# TT1-1-Top.net
KiCad netlist of a schematic drawn in Altium Designer
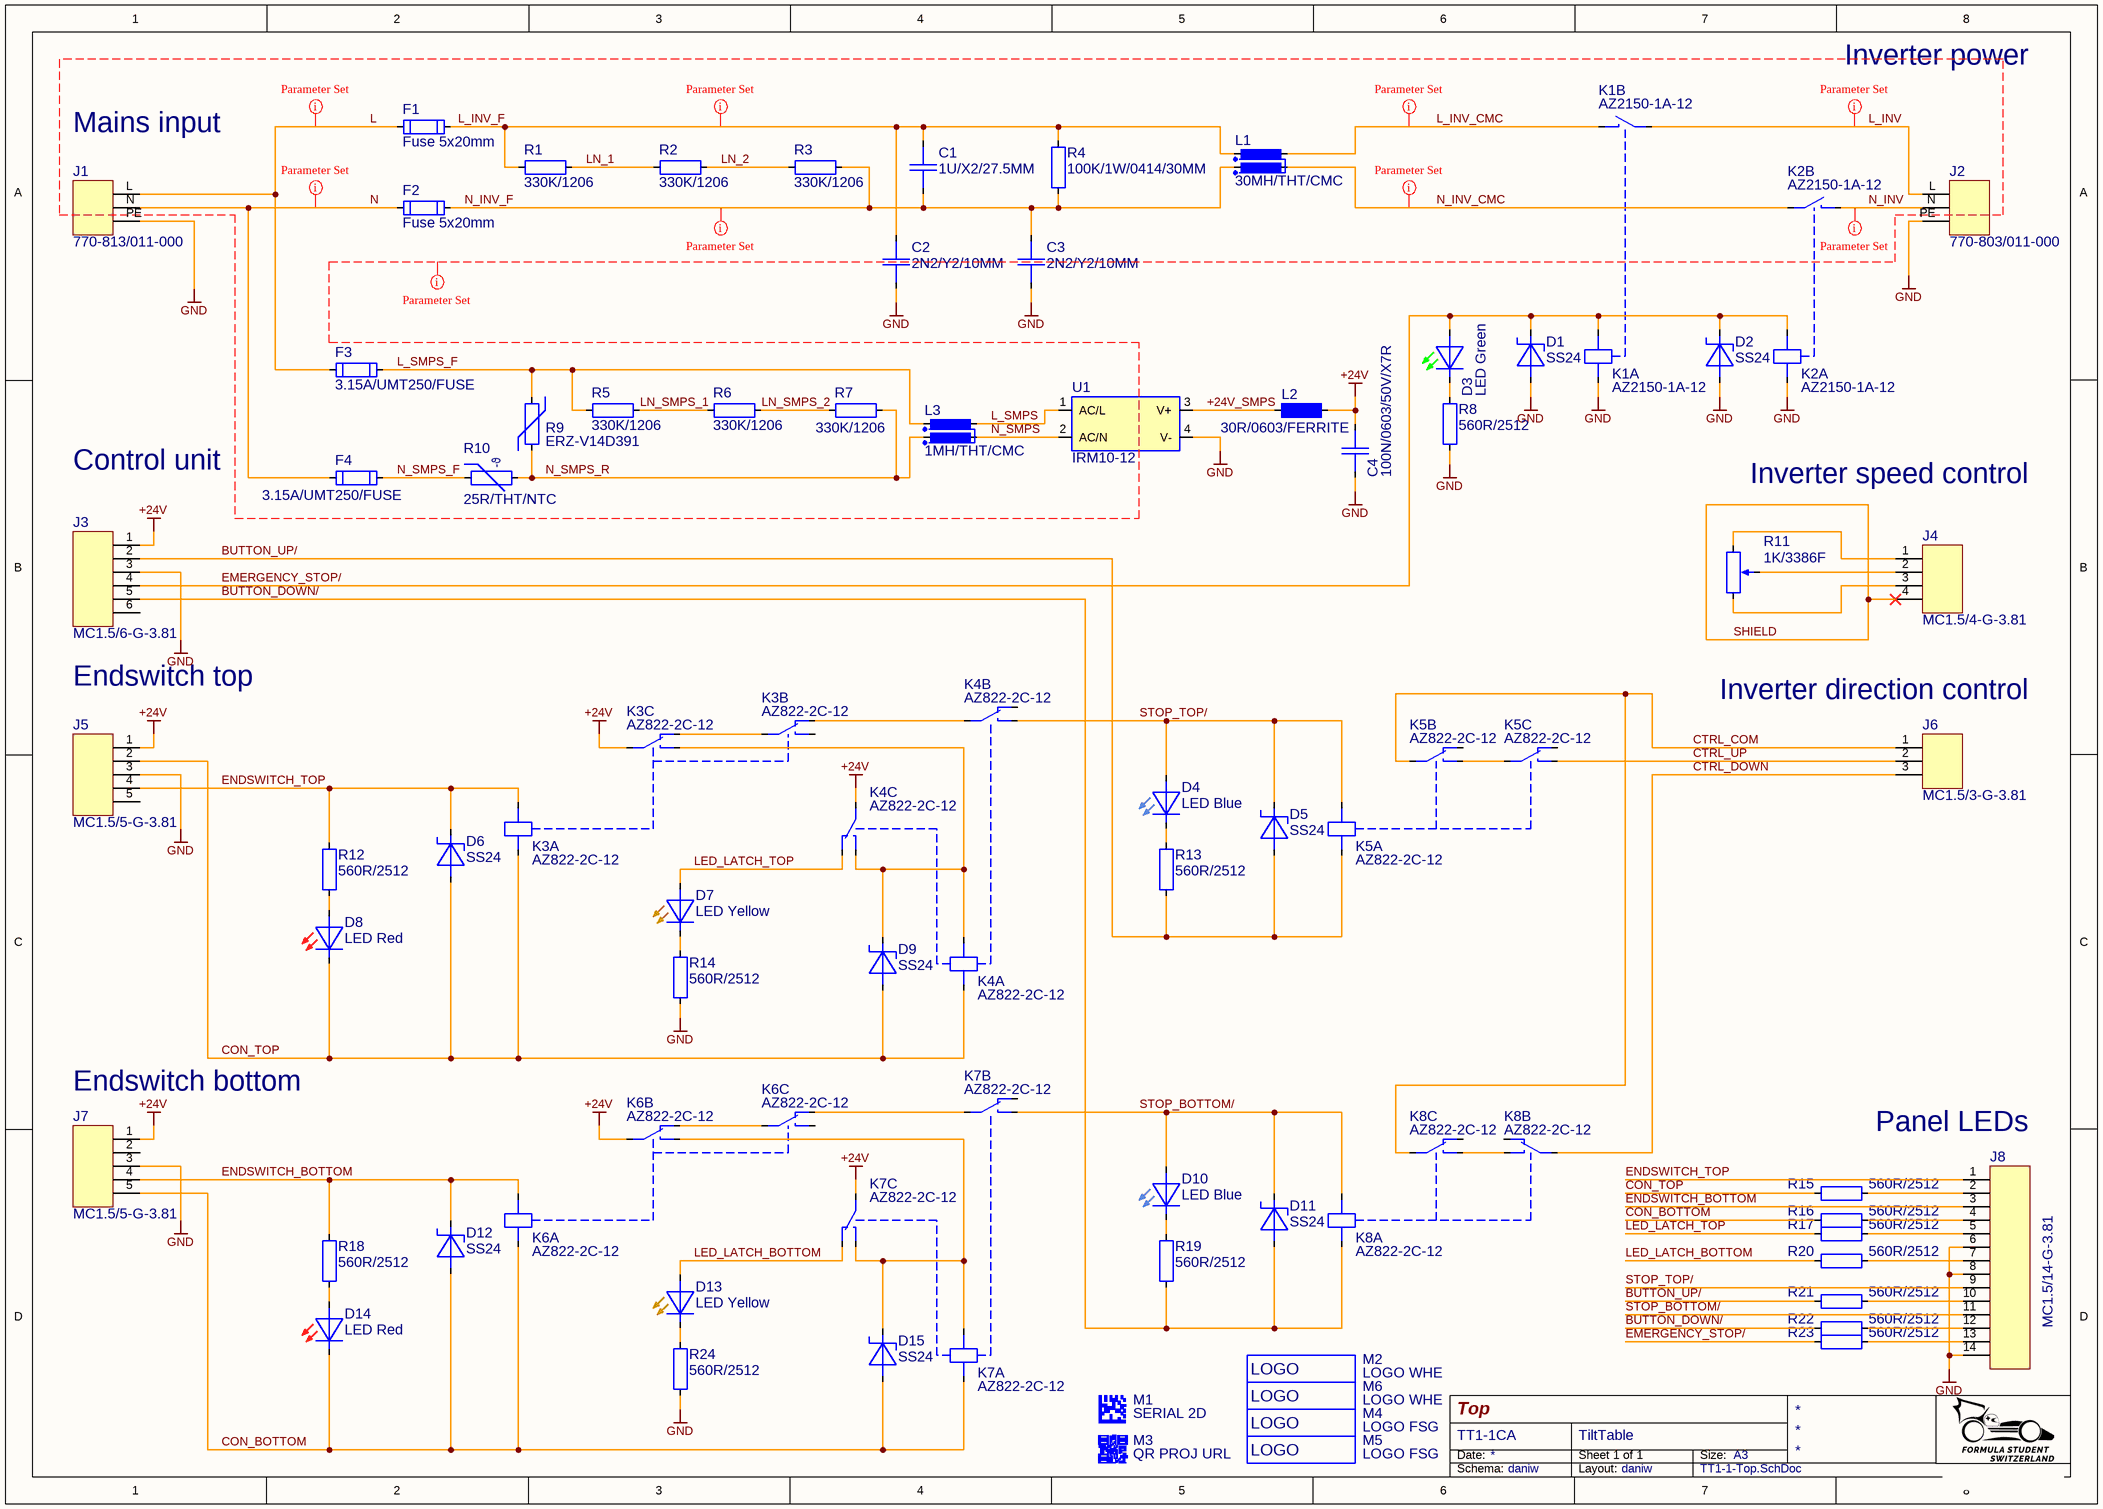
[diagram p0: TT1-1-Top.SchDoc]

(export (version "E")
  (design (tool "Eeschema 10.0.6"))
  (components
    (comp (ref "C1")
      (value "1U/X2/27.5MM")
      (footprint "CAP2750P315X110X190-BL")
      (description "CAP THT 31.5X11X19 1uF 305V X2")
      (fields (field (name "MANUFACTURER") "GENERIC"))
      (libsource (lib "daniw_altium_lib") (part "C"))
    )
    (comp (ref "C2")
      (value "2N2/Y2/10MM")
      (footprint "CAP1000P130X40X90-BL")
      (description "CAP THT 13X4X9 2.2nF 300V Y2")
      (fields (field (name "MANUFACTURER") "GENERIC"))
      (libsource (lib "daniw_altium_lib") (part "C"))
    )
    (comp (ref "C3")
      (value "2N2/Y2/10MM")
      (footprint "CAP1000P130X40X90-BL")
      (description "CAP THT 13X4X9 2.2nF 300V Y2")
      (fields (field (name "MANUFACTURER") "GENERIC"))
      (libsource (lib "daniw_altium_lib") (part "C"))
    )
    (comp (ref "C4")
      (value "100N/0603/50V/X7R")
      (footprint "CAP0603_X7R")
      (description "CAP SM 0603 100nF 50V X7R")
      (fields (field (name "MANUFACTURER") "GENERIC"))
      (libsource (lib "daniw_altium_lib") (part "C"))
    )
    (comp (ref "D1")
      (value "SS24")
      (footprint "DIOM5226X230")
      (description "Si Shottky Diode 2A DO-214AC")
      (fields (field (name "MANUFACTURER") "MSKSEMI"))
      (libsource (lib "daniw_altium_lib") (part "D_Schottky"))
    )
    (comp (ref "D2")
      (value "SS24")
      (footprint "DIOM5226X230")
      (description "Si Shottky Diode 2A DO-214AC")
      (fields (field (name "MANUFACTURER") "MSKSEMI"))
      (libsource (lib "daniw_altium_lib") (part "D_Schottky"))
    )
    (comp (ref "D3")
      (value "LED Green")
      (footprint "LED0603_GREEN")
      (description "Generic LED Green 0603")
      (fields (field (name "PART NUMBER") "LED Green 0603") (field (name "MANUFACTURER") "GENERIC"))
      (libsource (lib "daniw_altium_lib") (part "LED_GREEN"))
    )
    (comp (ref "D4")
      (value "LED Blue")
      (footprint "LED0603_BLUE")
      (description "Generic LED Blue 0603")
      (fields (field (name "PART NUMBER") "LED Blue 0603") (field (name "MANUFACTURER") "GENERIC"))
      (libsource (lib "daniw_altium_lib") (part "LED_BLUE"))
    )
    (comp (ref "D5")
      (value "SS24")
      (footprint "DIOM5226X230")
      (description "Si Shottky Diode 2A DO-214AC")
      (fields (field (name "MANUFACTURER") "MSKSEMI"))
      (libsource (lib "daniw_altium_lib") (part "D_Schottky"))
    )
    (comp (ref "D6")
      (value "SS24")
      (footprint "DIOM5226X230")
      (description "Si Shottky Diode 2A DO-214AC")
      (fields (field (name "MANUFACTURER") "MSKSEMI"))
      (libsource (lib "daniw_altium_lib") (part "D_Schottky"))
    )
    (comp (ref "D7")
      (value "LED Yellow")
      (footprint "LED0603_YELLOW")
      (description "Generic LED Yellow 0603")
      (fields (field (name "PART NUMBER") "LED Yellow 0603") (field (name "MANUFACTURER") "GENERIC"))
      (libsource (lib "daniw_altium_lib") (part "LED_YELLOW"))
    )
    (comp (ref "D8")
      (value "LED Red")
      (footprint "LED0603_RED")
      (description "Generic LED Red 0603")
      (fields (field (name "PART NUMBER") "LED Red 0603") (field (name "MANUFACTURER") "GENERIC"))
      (libsource (lib "daniw_altium_lib") (part "LED_RED"))
    )
    (comp (ref "D9")
      (value "SS24")
      (footprint "DIOM5226X230")
      (description "Si Shottky Diode 2A DO-214AC")
      (fields (field (name "MANUFACTURER") "MSKSEMI"))
      (libsource (lib "daniw_altium_lib") (part "D_Schottky"))
    )
    (comp (ref "D10")
      (value "LED Blue")
      (footprint "LED0603_BLUE")
      (description "Generic LED Blue 0603")
      (fields (field (name "PART NUMBER") "LED Blue 0603") (field (name "MANUFACTURER") "GENERIC"))
      (libsource (lib "daniw_altium_lib") (part "LED_BLUE"))
    )
    (comp (ref "D11")
      (value "SS24")
      (footprint "DIOM5226X230")
      (description "Si Shottky Diode 2A DO-214AC")
      (fields (field (name "MANUFACTURER") "MSKSEMI"))
      (libsource (lib "daniw_altium_lib") (part "D_Schottky"))
    )
    (comp (ref "D12")
      (value "SS24")
      (footprint "DIOM5226X230")
      (description "Si Shottky Diode 2A DO-214AC")
      (fields (field (name "MANUFACTURER") "MSKSEMI"))
      (libsource (lib "daniw_altium_lib") (part "D_Schottky"))
    )
    (comp (ref "D13")
      (value "LED Yellow")
      (footprint "LED0603_YELLOW")
      (description "Generic LED Yellow 0603")
      (fields (field (name "PART NUMBER") "LED Yellow 0603") (field (name "MANUFACTURER") "GENERIC"))
      (libsource (lib "daniw_altium_lib") (part "LED_YELLOW"))
    )
    (comp (ref "D14")
      (value "LED Red")
      (footprint "LED0603_RED")
      (description "Generic LED Red 0603")
      (fields (field (name "PART NUMBER") "LED Red 0603") (field (name "MANUFACTURER") "GENERIC"))
      (libsource (lib "daniw_altium_lib") (part "LED_RED"))
    )
    (comp (ref "D15")
      (value "SS24")
      (footprint "DIOM5226X230")
      (description "Si Shottky Diode 2A DO-214AC")
      (fields (field (name "MANUFACTURER") "MSKSEMI"))
      (libsource (lib "daniw_altium_lib") (part "D_Schottky"))
    )
    (comp (ref "F1")
      (value "Fuse 5x20mm")
      (footprint "OGN_THR")
      (description "open fuse holder, 5 x 20 mm, THR, IEC 60335-1")
      (fields (field (name "PART NUMBER") "Fuse/5x20mm/OGN") (field (name "MANUFACTURER") "Schurter"))
      (libsource (lib "daniw_altium_lib") (part "Fuse"))
    )
    (comp (ref "F2")
      (value "Fuse 5x20mm")
      (footprint "OGN_THR")
      (description "open fuse holder, 5 x 20 mm, THR, IEC 60335-1")
      (fields (field (name "PART NUMBER") "Fuse/5x20mm/OGN") (field (name "MANUFACTURER") "Schurter"))
      (libsource (lib "daniw_altium_lib") (part "Fuse"))
    )
    (comp (ref "F3")
      (value "3.15A/UMT250/FUSE")
      (footprint "UMT250")
      (description "Fuse 250VAC 3.15A UMT250")
      (fields (field (name "MANUFACTURER") "Schurter"))
      (libsource (lib "daniw_altium_lib") (part "Fuse"))
    )
    (comp (ref "F4")
      (value "3.15A/UMT250/FUSE")
      (footprint "UMT250")
      (description "Fuse 250VAC 3.15A UMT250")
      (fields (field (name "MANUFACTURER") "Schurter"))
      (libsource (lib "daniw_altium_lib") (part "Fuse"))
    )
    (comp (ref "J1")
      (value "770-813/011-000")
      (footprint "770-813/011-000")
      (description "Wago 770-813/011-000")
      (fields (field (name "MANUFACTURER") "Wago"))
      (libsource (lib "daniw_altium_lib") (part "CON3_MAINS"))
    )
    (comp (ref "J2")
      (value "770-803/011-000")
      (footprint "770-803/011-000")
      (description "Wago 770-803/011-000")
      (fields (field (name "MANUFACTURER") "Wago"))
      (libsource (lib "") (part "CON3_MAINS_1"))
    )
    (comp (ref "J3")
      (value "MC1.5/6-G-3.81")
      (footprint "MC1.5/6-G-3.81")
      (description "Phoenix contact MC 1,5/ 6-G-3,81")
      (fields (field (name "MANUFACTURER") "Phoenix"))
      (libsource (lib "daniw_altium_lib") (part "CON6"))
    )
    (comp (ref "J4")
      (value "MC1.5/4-G-3.81")
      (footprint "MC1.5/4-G-3.81")
      (description "Phoenix contact MC 1,5/ 4-G-3,81")
      (fields (field (name "MANUFACTURER") "Phoenix"))
      (libsource (lib "daniw_altium_lib") (part "CON4"))
    )
    (comp (ref "J5")
      (value "MC1.5/5-G-3.81")
      (footprint "MC1.5/5-G-3.81")
      (description "Phoenix contact MC 1,5/ 5-G-3,81")
      (fields (field (name "MANUFACTURER") "Phoenix"))
      (libsource (lib "daniw_altium_lib") (part "CON5"))
    )
    (comp (ref "J6")
      (value "MC1.5/3-G-3.81")
      (footprint "MC1.5/3-G-3.81")
      (description "Phoenix contact MC 1,5/ 3-G-3,81")
      (fields (field (name "MANUFACTURER") "Phoenix"))
      (libsource (lib "daniw_altium_lib") (part "CON3"))
    )
    (comp (ref "J7")
      (value "MC1.5/5-G-3.81")
      (footprint "MC1.5/5-G-3.81")
      (description "Phoenix contact MC 1,5/ 5-G-3,81")
      (fields (field (name "MANUFACTURER") "Phoenix"))
      (libsource (lib "daniw_altium_lib") (part "CON5"))
    )
    (comp (ref "J8")
      (value "MC1.5/14-G-3.81")
      (footprint "MC1.5/14-G-3.81")
      (description "Phoenix contact MC 1,5/ 14-G-3,81")
      (fields (field (name "MANUFACTURER") "Phoenix"))
      (libsource (lib "daniw_altium_lib") (part "CON14"))
    )
    (comp (ref "K1")
      (value "AZ2150-1A-12")
      (footprint "AZ2150-SPST-NO")
      (description "Miniature Power Relay, SPST-NO, 12V Coil, 40A 30VDC 300VAC")
      (fields (field (name "MANUFACTURER") "Zettler"))
      (libsource (lib "daniw_altium_lib") (part "REL_SPST_NO"))
    )
    (comp (ref "K2")
      (value "AZ2150-1A-12")
      (footprint "AZ2150-SPST-NO")
      (description "Miniature Power Relay, SPST-NO, 12V Coil, 40A 30VDC 300VAC")
      (fields (field (name "MANUFACTURER") "Zettler"))
      (libsource (lib "daniw_altium_lib") (part "REL_SPST_NO"))
    )
    (comp (ref "K3")
      (value "AZ822-2C-12")
      (footprint "AZ822")
      (description "Subminiature DIP Relay, DPDT, 12V 98mW Coil, 2A 220VDC 250VAC")
      (fields (field (name "MANUFACTURER") "Zettler"))
      (libsource (lib "daniw_altium_lib") (part "REL_DPDT"))
    )
    (comp (ref "K4")
      (value "AZ822-2C-12")
      (footprint "AZ822")
      (description "Subminiature DIP Relay, DPDT, 12V 98mW Coil, 2A 220VDC 250VAC")
      (fields (field (name "MANUFACTURER") "Zettler"))
      (libsource (lib "daniw_altium_lib") (part "REL_DPDT"))
    )
    (comp (ref "K5")
      (value "AZ822-2C-12")
      (footprint "AZ822")
      (description "Subminiature DIP Relay, DPDT, 12V 98mW Coil, 2A 220VDC 250VAC")
      (fields (field (name "MANUFACTURER") "Zettler"))
      (libsource (lib "daniw_altium_lib") (part "REL_DPDT"))
    )
    (comp (ref "K6")
      (value "AZ822-2C-12")
      (footprint "AZ822")
      (description "Subminiature DIP Relay, DPDT, 12V 98mW Coil, 2A 220VDC 250VAC")
      (fields (field (name "MANUFACTURER") "Zettler"))
      (libsource (lib "daniw_altium_lib") (part "REL_DPDT"))
    )
    (comp (ref "K7")
      (value "AZ822-2C-12")
      (footprint "AZ822")
      (description "Subminiature DIP Relay, DPDT, 12V 98mW Coil, 2A 220VDC 250VAC")
      (fields (field (name "MANUFACTURER") "Zettler"))
      (libsource (lib "daniw_altium_lib") (part "REL_DPDT"))
    )
    (comp (ref "K8")
      (value "AZ822-2C-12")
      (footprint "AZ822")
      (description "Subminiature DIP Relay, DPDT, 12V 98mW Coil, 2A 220VDC 250VAC")
      (fields (field (name "MANUFACTURER") "Zettler"))
      (libsource (lib "daniw_altium_lib") (part "REL_DPDT"))
    )
    (comp (ref "L1")
      (value "30MH/THT/CMC")
      (footprint "CMC-WE-CMBNC-XL-7448050530")
      (description "CMC 30mH 5A Würth CMBNC 7448050530")
      (fields (field (name "MANUFACTURER") "Würth"))
      (libsource (lib "daniw_altium_lib") (part "L_CMC_2"))
    )
    (comp (ref "L2")
      (value "30R/0603/FERRITE")
      (footprint "FB0603")
      (description "30R@100MHz 5A 0603 Ferrite")
      (fields (field (name "MANUFACTURER") "GENERIC"))
      (libsource (lib "daniw_altium_lib") (part "Ferrite"))
    )
    (comp (ref "L3")
      (value "1MH/THT/CMC")
      (footprint "DFKH-CASE-50-2")
      (description "CMC 1mH 2A THT Schurter DFKH-14-0003")
      (fields (field (name "MANUFACTURER") "SCHURTER"))
      (libsource (lib "daniw_altium_lib") (part "L_CMC_2"))
    )
    (comp (ref "M1")
      (value "SERIAL 2D")
      (footprint "SERIAL-2D-8MM-RESTRICT")
      (description "2D Serial number placeholder, Dotmatrix or QR, size: 8mm, restriction on top layer")
      (fields (field (name "PART NUMBER") "SERIAL 2D 8MM RESTRICT") (field (name "MANUFACTURER") "NONE"))
      (libsource (lib "daniw_altium_lib") (part "SERIAL-2D"))
    )
    (comp (ref "M2")
      (value "LOGO WHE")
      (footprint "LOGO-WHE-10MM")
      (description "WHE logo, size 10mm")
      (fields (field (name "PART NUMBER") "LOGO WHE 10MM") (field (name "MANUFACTURER") "NONE"))
      (libsource (lib "daniw_altium_lib") (part "LOGO"))
    )
    (comp (ref "M3")
      (value "QR PROJ URL")
      (footprint "QR-PROJECT-URL-10MM")
      (description "QR Code, Project URL, 10mm")
      (fields (field (name "PART NUMBER") "QR PROJ URL 10MM") (field (name "MANUFACTURER") "NONE"))
      (libsource (lib "daniw_altium_lib") (part "QR-PROJ-URL"))
    )
    (comp (ref "M4")
      (value "LOGO FSG")
      (footprint "LOGO-FSG-15MM")
      (description "FSG logo, size 15mm")
      (fields (field (name "PART NUMBER") "LOGO FSG 15MM") (field (name "MANUFACTURER") "NONE"))
      (libsource (lib "daniw_altium_lib") (part "LOGO"))
    )
    (comp (ref "M5")
      (value "LOGO FSG")
      (footprint "LOGO-FSG-20MM")
      (description "FSG logo, size 20mm")
      (fields (field (name "PART NUMBER") "LOGO FSG 20MM") (field (name "MANUFACTURER") "NONE"))
      (libsource (lib "daniw_altium_lib") (part "LOGO"))
    )
    (comp (ref "M6")
      (value "LOGO WHE")
      (footprint "LOGO-WHE-20MM")
      (description "WHE logo, size 20mm")
      (fields (field (name "PART NUMBER") "LOGO WHE 20MM") (field (name "MANUFACTURER") "NONE"))
      (libsource (lib "daniw_altium_lib") (part "LOGO"))
    )
    (comp (ref "R1")
      (value "330K/1206")
      (footprint "R1206-0.80-WW")
      (description "RES SM 1206 330K")
      (fields (field (name "MANUFACTURER") "GENERIC"))
      (libsource (lib "daniw_altium_lib") (part "R"))
    )
    (comp (ref "R2")
      (value "330K/1206")
      (footprint "R1206-0.80-WW")
      (description "RES SM 1206 330K")
      (fields (field (name "MANUFACTURER") "GENERIC"))
      (libsource (lib "daniw_altium_lib") (part "R"))
    )
    (comp (ref "R3")
      (value "330K/1206")
      (footprint "R1206-0.80-WW")
      (description "RES SM 1206 330K")
      (fields (field (name "MANUFACTURER") "GENERIC"))
      (libsource (lib "daniw_altium_lib") (part "R"))
    )
    (comp (ref "R4")
      (value "100K/1W/0414/30MM")
      (footprint "RESAD3000W80L1200D400B")
      (description "RES TH 1W 0414 30MM 100K")
      (fields (field (name "MANUFACTURER") "GENERIC"))
      (libsource (lib "daniw_altium_lib") (part "R"))
    )
    (comp (ref "R5")
      (value "330K/1206")
      (footprint "R1206-0.80-WW")
      (description "RES SM 1206 330K")
      (fields (field (name "MANUFACTURER") "GENERIC"))
      (libsource (lib "daniw_altium_lib") (part "R"))
    )
    (comp (ref "R6")
      (value "330K/1206")
      (footprint "R1206-0.80-WW")
      (description "RES SM 1206 330K")
      (fields (field (name "MANUFACTURER") "GENERIC"))
      (libsource (lib "daniw_altium_lib") (part "R"))
    )
    (comp (ref "R7")
      (value "330K/1206")
      (footprint "R1206-0.80-WW")
      (description "RES SM 1206 330K")
      (fields (field (name "MANUFACTURER") "GENERIC"))
      (libsource (lib "daniw_altium_lib") (part "R"))
    )
    (comp (ref "R8")
      (value "560R/2512")
      (footprint "R2512-0.65-WW")
      (description "RES SM 2512 560R")
      (fields (field (name "MANUFACTURER") "GENERIC"))
      (libsource (lib "daniw_altium_lib") (part "R"))
    )
    (comp (ref "R9")
      (value "ERZ-V14D391")
      (footprint "RESD750W80D155")
      (description "VARISTOR 391V 6kA")
      (fields (field (name "MANUFACTURER") "GENERIC"))
      (libsource (lib "daniw_altium_lib") (part "R_VAR"))
    )
    (comp (ref "R10")
      (value "25R/THT/NTC")
      (footprint "RESD500W60D115")
      (description "RES NTC THT 5 25R")
      (fields (field (name "MANUFACTURER") "GENERIC"))
      (libsource (lib "daniw_altium_lib") (part "R_NTC"))
    )
    (comp (ref "R11")
      (value "1K/3386F")
      (footprint "3386F")
      (description "RES POT 3386F 1K")
      (fields (field (name "MANUFACTURER") "Bourns"))
      (libsource (lib "daniw_altium_lib") (part "R_POT"))
    )
    (comp (ref "R12")
      (value "560R/2512")
      (footprint "R2512-0.65-WW")
      (description "RES SM 2512 560R")
      (fields (field (name "MANUFACTURER") "GENERIC"))
      (libsource (lib "daniw_altium_lib") (part "R"))
    )
    (comp (ref "R13")
      (value "560R/2512")
      (footprint "R2512-0.65-WW")
      (description "RES SM 2512 560R")
      (fields (field (name "MANUFACTURER") "GENERIC"))
      (libsource (lib "daniw_altium_lib") (part "R"))
    )
    (comp (ref "R14")
      (value "560R/2512")
      (footprint "R2512-0.65-WW")
      (description "RES SM 2512 560R")
      (fields (field (name "MANUFACTURER") "GENERIC"))
      (libsource (lib "daniw_altium_lib") (part "R"))
    )
    (comp (ref "R15")
      (value "560R/2512")
      (footprint "R2512-0.65-WW")
      (description "RES SM 2512 560R")
      (fields (field (name "MANUFACTURER") "GENERIC"))
      (libsource (lib "daniw_altium_lib") (part "R"))
    )
    (comp (ref "R16")
      (value "560R/2512")
      (footprint "R2512-0.65-WW")
      (description "RES SM 2512 560R")
      (fields (field (name "MANUFACTURER") "GENERIC"))
      (libsource (lib "daniw_altium_lib") (part "R"))
    )
    (comp (ref "R17")
      (value "560R/2512")
      (footprint "R2512-0.65-WW")
      (description "RES SM 2512 560R")
      (fields (field (name "MANUFACTURER") "GENERIC"))
      (libsource (lib "daniw_altium_lib") (part "R"))
    )
    (comp (ref "R18")
      (value "560R/2512")
      (footprint "R2512-0.65-WW")
      (description "RES SM 2512 560R")
      (fields (field (name "MANUFACTURER") "GENERIC"))
      (libsource (lib "daniw_altium_lib") (part "R"))
    )
    (comp (ref "R19")
      (value "560R/2512")
      (footprint "R2512-0.65-WW")
      (description "RES SM 2512 560R")
      (fields (field (name "MANUFACTURER") "GENERIC"))
      (libsource (lib "daniw_altium_lib") (part "R"))
    )
    (comp (ref "R20")
      (value "560R/2512")
      (footprint "R2512-0.65-WW")
      (description "RES SM 2512 560R")
      (fields (field (name "MANUFACTURER") "GENERIC"))
      (libsource (lib "daniw_altium_lib") (part "R"))
    )
    (comp (ref "R21")
      (value "560R/2512")
      (footprint "R2512-0.65-WW")
      (description "RES SM 2512 560R")
      (fields (field (name "MANUFACTURER") "GENERIC"))
      (libsource (lib "daniw_altium_lib") (part "R"))
    )
    (comp (ref "R22")
      (value "560R/2512")
      (footprint "R2512-0.65-WW")
      (description "RES SM 2512 560R")
      (fields (field (name "MANUFACTURER") "GENERIC"))
      (libsource (lib "daniw_altium_lib") (part "R"))
    )
    (comp (ref "R23")
      (value "560R/2512")
      (footprint "R2512-0.65-WW")
      (description "RES SM 2512 560R")
      (fields (field (name "MANUFACTURER") "GENERIC"))
      (libsource (lib "daniw_altium_lib") (part "R"))
    )
    (comp (ref "R24")
      (value "560R/2512")
      (footprint "R2512-0.65-WW")
      (description "RES SM 2512 560R")
      (fields (field (name "MANUFACTURER") "GENERIC"))
      (libsource (lib "daniw_altium_lib") (part "R"))
    )
    (comp (ref "U1")
      (value "IRM10-12")
      (footprint "IRM10")
      (description "10W AC-DC PCB-Mount Green Power Module, 12V")
      (fields (field (name "MANUFACTURER") "Meanwell"))
      (libsource (lib "daniw_altium_lib") (part "IRM30"))
    )
  )
  (nets
    (net (code "1") (name "+24V") (class "Default")
      (node (ref "C4") (pin "1") (pinfunction "1_1") (pintype "passive"))
      (node (ref "J3") (pin "1") (pintype "passive"))
      (node (ref "J5") (pin "1") (pintype "passive"))
      (node (ref "J7") (pin "1") (pintype "passive"))
      (node (ref "K3") (pin "6") (pinfunction "COM2_6") (pintype "passive"))
      (node (ref "K4") (pin "6") (pinfunction "COM2_6") (pintype "passive"))
      (node (ref "K6") (pin "3") (pinfunction "COM1_3") (pintype "passive"))
      (node (ref "K7") (pin "6") (pinfunction "COM2_6") (pintype "passive"))
      (node (ref "L2") (pin "2") (pinfunction "2_2") (pintype "passive"))
    )
    (net (code "2") (name "/+24V_SMPS") (class "Default")
      (node (ref "L2") (pin "1") (pinfunction "1_1") (pintype "passive"))
      (node (ref "U1") (pin "3") (pinfunction "V+_3") (pintype "passive"))
    )
    (net (code "3") (name "/BUTTON_DOWN{slash}") (class "Default")
      (node (ref "D11") (pin "2") (pinfunction "2_2") (pintype "passive"))
      (node (ref "J3") (pin "5") (pintype "passive"))
      (node (ref "K8") (pin "2") (pinfunction "2_2") (pintype "passive"))
      (node (ref "R19") (pin "2") (pinfunction "2_2") (pintype "passive"))
      (node (ref "R22") (pin "1") (pinfunction "1_1") (pintype "passive"))
    )
    (net (code "4") (name "/BUTTON_UP{slash}") (class "Default")
      (node (ref "D5") (pin "2") (pinfunction "2_2") (pintype "passive"))
      (node (ref "J3") (pin "2") (pintype "passive"))
      (node (ref "K5") (pin "1") (pinfunction "1_1") (pintype "passive"))
      (node (ref "R13") (pin "2") (pinfunction "2_2") (pintype "passive"))
      (node (ref "R21") (pin "1") (pinfunction "1_1") (pintype "passive"))
    )
    (net (code "5") (name "/CON_BOTTOM") (class "Default")
      (node (ref "D12") (pin "2") (pinfunction "2_2") (pintype "passive"))
      (node (ref "D14") (pin "1") (pinfunction "1_1") (pintype "passive"))
      (node (ref "D15") (pin "2") (pinfunction "2_2") (pintype "passive"))
      (node (ref "J7") (pin "5") (pintype "passive"))
      (node (ref "K6") (pin "2") (pinfunction "2_2") (pintype "passive"))
      (node (ref "K7") (pin "2") (pinfunction "2_2") (pintype "passive"))
      (node (ref "R16") (pin "1") (pinfunction "1_1") (pintype "passive"))
    )
    (net (code "6") (name "/CON_TOP") (class "Default")
      (node (ref "D6") (pin "2") (pinfunction "2_2") (pintype "passive"))
      (node (ref "D8") (pin "1") (pinfunction "1_1") (pintype "passive"))
      (node (ref "D9") (pin "2") (pinfunction "2_2") (pintype "passive"))
      (node (ref "J5") (pin "2") (pintype "passive"))
      (node (ref "K3") (pin "2") (pinfunction "2_2") (pintype "passive"))
      (node (ref "K4") (pin "2") (pinfunction "2_2") (pintype "passive"))
      (node (ref "R15") (pin "1") (pinfunction "1_1") (pintype "passive"))
    )
    (net (code "7") (name "/CTRL_COM") (class "Default")
      (node (ref "J6") (pin "1") (pintype "passive"))
      (node (ref "K5") (pin "3") (pinfunction "COM1_3") (pintype "passive"))
      (node (ref "K8") (pin "6") (pinfunction "COM2_6") (pintype "passive"))
    )
    (net (code "8") (name "/CTRL_DOWN") (class "Default")
      (node (ref "J6") (pin "3") (pintype "passive"))
      (node (ref "K8") (pin "3") (pinfunction "COM1_3") (pintype "passive"))
    )
    (net (code "9") (name "/CTRL_UP") (class "Default")
      (node (ref "J6") (pin "2") (pintype "passive"))
      (node (ref "K5") (pin "8") (pinfunction "NO2_8") (pintype "passive"))
    )
    (net (code "10") (name "/EMERGENCY_STOP{slash}") (class "Default")
      (node (ref "D1") (pin "1") (pinfunction "1_1") (pintype "passive"))
      (node (ref "D2") (pin "1") (pinfunction "1_1") (pintype "passive"))
      (node (ref "D3") (pin "2") (pinfunction "2_2") (pintype "passive"))
      (node (ref "J3") (pin "4") (pintype "passive"))
      (node (ref "K1") (pin "1") (pinfunction "1_1") (pintype "passive"))
      (node (ref "K2") (pin "1") (pinfunction "1_1") (pintype "passive"))
      (node (ref "R23") (pin "1") (pinfunction "1_1") (pintype "passive"))
    )
    (net (code "11") (name "/ENDSWITCH_BOTTOM") (class "Default")
      (node (ref "D12") (pin "1") (pinfunction "1_1") (pintype "passive"))
      (node (ref "J7") (pin "4") (pintype "passive"))
      (node (ref "J8") (pin "3") (pintype "passive"))
      (node (ref "K6") (pin "1") (pinfunction "1_1") (pintype "passive"))
      (node (ref "R18") (pin "1") (pinfunction "1_1") (pintype "passive"))
    )
    (net (code "12") (name "/ENDSWITCH_TOP") (class "Default")
      (node (ref "D6") (pin "1") (pinfunction "1_1") (pintype "passive"))
      (node (ref "J5") (pin "4") (pintype "passive"))
      (node (ref "J8") (pin "1") (pintype "passive"))
      (node (ref "K3") (pin "1") (pinfunction "1_1") (pintype "passive"))
      (node (ref "R12") (pin "1") (pinfunction "1_1") (pintype "passive"))
    )
    (net (code "13") (name "/L") (class "Default")
      (node (ref "F1") (pin "1") (pinfunction "1_1") (pintype "passive"))
      (node (ref "F3") (pin "1") (pinfunction "1_1") (pintype "passive"))
      (node (ref "J1") (pin "L") (pintype "passive"))
    )
    (net (code "14") (name "/LED_LATCH_BOTTOM") (class "Default")
      (node (ref "D13") (pin "2") (pinfunction "2_2") (pintype "passive"))
      (node (ref "K7") (pin "7") (pinfunction "NC2_7") (pintype "passive"))
      (node (ref "R20") (pin "1") (pinfunction "1_1") (pintype "passive"))
    )
    (net (code "15") (name "/LED_LATCH_TOP") (class "Default")
      (node (ref "D7") (pin "2") (pinfunction "2_2") (pintype "passive"))
      (node (ref "K4") (pin "7") (pinfunction "NC2_7") (pintype "passive"))
      (node (ref "R17") (pin "1") (pinfunction "1_1") (pintype "passive"))
    )
    (net (code "16") (name "/LN_1") (class "Default")
      (node (ref "R1") (pin "2") (pinfunction "2_2") (pintype "passive"))
      (node (ref "R2") (pin "1") (pinfunction "1_1") (pintype "passive"))
    )
    (net (code "17") (name "/LN_2") (class "Default")
      (node (ref "R2") (pin "2") (pinfunction "2_2") (pintype "passive"))
      (node (ref "R3") (pin "1") (pinfunction "1_1") (pintype "passive"))
    )
    (net (code "18") (name "/LN_SMPS_1") (class "Default")
      (node (ref "R5") (pin "2") (pinfunction "2_2") (pintype "passive"))
      (node (ref "R6") (pin "2") (pinfunction "2_2") (pintype "passive"))
    )
    (net (code "19") (name "/LN_SMPS_2") (class "Default")
      (node (ref "R6") (pin "1") (pinfunction "1_1") (pintype "passive"))
      (node (ref "R7") (pin "1") (pinfunction "1_1") (pintype "passive"))
    )
    (net (code "20") (name "/L_INV") (class "Default")
      (node (ref "J2") (pin "L") (pintype "passive"))
      (node (ref "K1") (pin "3") (pinfunction "COM1_3") (pintype "passive"))
    )
    (net (code "21") (name "/L_INV_CMC") (class "Default")
      (node (ref "K1") (pin "4") (pinfunction "NO1_4") (pintype "passive"))
      (node (ref "L1") (pin "3") (pinfunction "3_3") (pintype "passive"))
    )
    (net (code "22") (name "/L_INV_F") (class "Default")
      (node (ref "C1") (pin "1") (pinfunction "1_1") (pintype "passive"))
      (node (ref "C2") (pin "1") (pinfunction "1_1") (pintype "passive"))
      (node (ref "F1") (pin "2") (pinfunction "2_2") (pintype "passive"))
      (node (ref "L1") (pin "1") (pinfunction "1_1") (pintype "passive"))
      (node (ref "R1") (pin "1") (pinfunction "1_1") (pintype "passive"))
      (node (ref "R4") (pin "1") (pinfunction "1_1") (pintype "passive"))
    )
    (net (code "23") (name "/L_SMPS") (class "Default")
      (node (ref "L3") (pin "3") (pinfunction "3_3") (pintype "passive"))
      (node (ref "U1") (pin "1") (pinfunction "AC/L_1") (pintype "passive"))
    )
    (net (code "24") (name "/L_SMPS_F") (class "Default")
      (node (ref "F3") (pin "2") (pinfunction "2_2") (pintype "passive"))
      (node (ref "L3") (pin "1") (pinfunction "1_1") (pintype "passive"))
      (node (ref "R5") (pin "1") (pinfunction "1_1") (pintype "passive"))
      (node (ref "R9") (pin "1") (pinfunction "1_1") (pintype "passive"))
    )
    (net (code "25") (name "/N") (class "Default")
      (node (ref "F2") (pin "1") (pinfunction "1_1") (pintype "passive"))
      (node (ref "F4") (pin "1") (pinfunction "1_1") (pintype "passive"))
      (node (ref "J1") (pin "N") (pintype "passive"))
    )
    (net (code "26") (name "/N_INV") (class "Default")
      (node (ref "J2") (pin "N") (pintype "passive"))
      (node (ref "K2") (pin "4") (pinfunction "NO1_4") (pintype "passive"))
    )
    (net (code "27") (name "/N_INV_CMC") (class "Default")
      (node (ref "K2") (pin "3") (pinfunction "COM1_3") (pintype "passive"))
      (node (ref "L1") (pin "4") (pinfunction "4_4") (pintype "passive"))
    )
    (net (code "28") (name "/N_INV_F") (class "Default")
      (node (ref "C1") (pin "2") (pinfunction "2_2") (pintype "passive"))
      (node (ref "C3") (pin "1") (pinfunction "1_1") (pintype "passive"))
      (node (ref "F2") (pin "2") (pinfunction "2_2") (pintype "passive"))
      (node (ref "L1") (pin "2") (pinfunction "2_2") (pintype "passive"))
      (node (ref "R3") (pin "2") (pinfunction "2_2") (pintype "passive"))
      (node (ref "R4") (pin "2") (pinfunction "2_2") (pintype "passive"))
    )
    (net (code "29") (name "/N_SMPS") (class "Default")
      (node (ref "L3") (pin "4") (pinfunction "4_4") (pintype "passive"))
      (node (ref "U1") (pin "2") (pinfunction "AC/N_2") (pintype "passive"))
    )
    (net (code "30") (name "/N_SMPS_F") (class "Default")
      (node (ref "F4") (pin "2") (pinfunction "2_2") (pintype "passive"))
      (node (ref "R10") (pin "1") (pinfunction "1_1") (pintype "passive"))
    )
    (net (code "31") (name "/N_SMPS_R") (class "Default")
      (node (ref "L3") (pin "2") (pinfunction "2_2") (pintype "passive"))
      (node (ref "R10") (pin "2") (pinfunction "2_2") (pintype "passive"))
      (node (ref "R7") (pin "2") (pinfunction "2_2") (pintype "passive"))
      (node (ref "R9") (pin "2") (pinfunction "2_2") (pintype "passive"))
    )
    (net (code "32") (name "/SHIELD") (class "Default")
      (node (ref "J4") (pin "4") (pintype "passive+no_connect"))
    )
    (net (code "33") (name "/STOP_BOTTOM{slash}") (class "Default")
      (node (ref "D10") (pin "2") (pinfunction "2_2") (pintype "passive"))
      (node (ref "D11") (pin "1") (pinfunction "1_1") (pintype "passive"))
      (node (ref "J8") (pin "11") (pintype "passive"))
      (node (ref "K7") (pin "5") (pinfunction "NO1_5") (pintype "passive"))
      (node (ref "K8") (pin "1") (pinfunction "1_1") (pintype "passive"))
    )
    (net (code "34") (name "/STOP_TOP{slash}") (class "Default")
      (node (ref "D4") (pin "2") (pinfunction "2_2") (pintype "passive"))
      (node (ref "D5") (pin "1") (pinfunction "1_1") (pintype "passive"))
      (node (ref "J8") (pin "9") (pintype "passive"))
      (node (ref "K4") (pin "5") (pinfunction "NO1_5") (pintype "passive"))
      (node (ref "K5") (pin "2") (pinfunction "2_2") (pintype "passive"))
    )
    (net (code "35") (name "GND") (class "Default")
      (node (ref "C2") (pin "2") (pinfunction "2_2") (pintype "passive"))
      (node (ref "C3") (pin "2") (pinfunction "2_2") (pintype "passive"))
      (node (ref "C4") (pin "2") (pinfunction "2_2") (pintype "passive"))
      (node (ref "D1") (pin "2") (pinfunction "2_2") (pintype "passive"))
      (node (ref "D2") (pin "2") (pinfunction "2_2") (pintype "passive"))
      (node (ref "J1") (pin "PE") (pintype "passive"))
      (node (ref "J2") (pin "PE") (pintype "passive"))
      (node (ref "J3") (pin "3") (pintype "passive"))
      (node (ref "J5") (pin "3") (pintype "passive"))
      (node (ref "J7") (pin "3") (pintype "passive"))
      (node (ref "J8") (pin "14") (pintype "passive"))
      (node (ref "J8") (pin "6") (pintype "passive"))
      (node (ref "J8") (pin "8") (pintype "passive"))
      (node (ref "K1") (pin "2") (pinfunction "2_2") (pintype "passive"))
      (node (ref "K2") (pin "2") (pinfunction "2_2") (pintype "passive"))
      (node (ref "R14") (pin "2") (pinfunction "2_2") (pintype "passive"))
      (node (ref "R24") (pin "2") (pinfunction "2_2") (pintype "passive"))
      (node (ref "R8") (pin "2") (pinfunction "2_2") (pintype "passive"))
      (node (ref "U1") (pin "4") (pinfunction "V-_4") (pintype "passive"))
    )
    (net (code "36") (name "Net-(D3-Pad1)") (class "Default")
      (node (ref "D3") (pin "1") (pinfunction "1_1") (pintype "passive"))
      (node (ref "R8") (pin "1") (pinfunction "1_1") (pintype "passive"))
    )
    (net (code "37") (name "Net-(D4-Pad1)") (class "Default")
      (node (ref "D4") (pin "1") (pinfunction "1_1") (pintype "passive"))
      (node (ref "R13") (pin "1") (pinfunction "1_1") (pintype "passive"))
    )
    (net (code "38") (name "Net-(D7-Pad1)") (class "Default")
      (node (ref "D7") (pin "1") (pinfunction "1_1") (pintype "passive"))
      (node (ref "R14") (pin "1") (pinfunction "1_1") (pintype "passive"))
    )
    (net (code "39") (name "Net-(D8-Pad2)") (class "Default")
      (node (ref "D8") (pin "2") (pinfunction "2_2") (pintype "passive"))
      (node (ref "R12") (pin "2") (pinfunction "2_2") (pintype "passive"))
    )
    (net (code "40") (name "Net-(D10-Pad1)") (class "Default")
      (node (ref "D10") (pin "1") (pinfunction "1_1") (pintype "passive"))
      (node (ref "R19") (pin "1") (pinfunction "1_1") (pintype "passive"))
    )
    (net (code "41") (name "Net-(D13-Pad1)") (class "Default")
      (node (ref "D13") (pin "1") (pinfunction "1_1") (pintype "passive"))
      (node (ref "R24") (pin "1") (pinfunction "1_1") (pintype "passive"))
    )
    (net (code "42") (name "Net-(D14-Pad2)") (class "Default")
      (node (ref "D14") (pin "2") (pinfunction "2_2") (pintype "passive"))
      (node (ref "R18") (pin "2") (pinfunction "2_2") (pintype "passive"))
    )
    (net (code "43") (name "Net-(J4-Pad1)") (class "Default")
      (node (ref "J4") (pin "1") (pintype "passive"))
      (node (ref "R11") (pin "2") (pinfunction "2_2") (pintype "passive"))
    )
    (net (code "44") (name "Net-(J4-Pad2)") (class "Default")
      (node (ref "J4") (pin "2") (pintype "passive"))
      (node (ref "R11") (pin "3") (pinfunction "3_3") (pintype "passive"))
    )
    (net (code "45") (name "Net-(J4-Pad3)") (class "Default")
      (node (ref "J4") (pin "3") (pintype "passive"))
      (node (ref "R11") (pin "1") (pinfunction "1_1") (pintype "passive"))
    )
    (net (code "46") (name "Net-(J8-Pad2)") (class "Default")
      (node (ref "J8") (pin "2") (pintype "passive"))
      (node (ref "R15") (pin "2") (pinfunction "2_2") (pintype "passive"))
    )
    (net (code "47") (name "Net-(J8-Pad4)") (class "Default")
      (node (ref "J8") (pin "4") (pintype "passive"))
      (node (ref "R16") (pin "2") (pinfunction "2_2") (pintype "passive"))
    )
    (net (code "48") (name "Net-(J8-Pad5)") (class "Default")
      (node (ref "J8") (pin "5") (pintype "passive"))
      (node (ref "R17") (pin "2") (pinfunction "2_2") (pintype "passive"))
    )
    (net (code "49") (name "Net-(J8-Pad7)") (class "Default")
      (node (ref "J8") (pin "7") (pintype "passive"))
      (node (ref "R20") (pin "2") (pinfunction "2_2") (pintype "passive"))
    )
    (net (code "50") (name "Net-(J8-Pad10)") (class "Default")
      (node (ref "J8") (pin "10") (pintype "passive"))
      (node (ref "R21") (pin "2") (pinfunction "2_2") (pintype "passive"))
    )
    (net (code "51") (name "Net-(J8-Pad12)") (class "Default")
      (node (ref "J8") (pin "12") (pintype "passive"))
      (node (ref "R22") (pin "2") (pinfunction "2_2") (pintype "passive"))
    )
    (net (code "52") (name "Net-(J8-Pad13)") (class "Default")
      (node (ref "J8") (pin "13") (pintype "passive"))
      (node (ref "R23") (pin "2") (pinfunction "2_2") (pintype "passive"))
    )
    (net (code "53") (name "Net-(K3B-COM1)") (class "Default")
      (node (ref "K3") (pin "3") (pinfunction "COM1_3") (pintype "passive"))
      (node (ref "K3") (pin "7") (pinfunction "NC2_7") (pintype "passive"))
    )
    (net (code "54") (name "Net-(K3B-NC1)") (class "Default")
      (node (ref "K3") (pin "4") (pinfunction "NC1_4") (pintype "passive"))
      (node (ref "K4") (pin "3") (pinfunction "COM1_3") (pintype "passive"))
    )
    (net (code "55") (name "Net-(K3C-NO2)") (class "Default")
      (node (ref "D9") (pin "1") (pinfunction "1_1") (pintype "passive"))
      (node (ref "K3") (pin "8") (pinfunction "NO2_8") (pintype "passive"))
      (node (ref "K4") (pin "1") (pinfunction "1_1") (pintype "passive"))
      (node (ref "K4") (pin "8") (pinfunction "NO2_8") (pintype "passive"))
    )
    (net (code "56") (name "Net-(K5B-NO1)") (class "Default")
      (node (ref "K5") (pin "5") (pinfunction "NO1_5") (pintype "passive"))
      (node (ref "K5") (pin "6") (pinfunction "COM2_6") (pintype "passive"))
    )
    (net (code "57") (name "Net-(K6B-NC1)") (class "Default")
      (node (ref "K6") (pin "4") (pinfunction "NC1_4") (pintype "passive"))
      (node (ref "K6") (pin "6") (pinfunction "COM2_6") (pintype "passive"))
    )
    (net (code "58") (name "Net-(K6B-NO1)") (class "Default")
      (node (ref "D15") (pin "1") (pinfunction "1_1") (pintype "passive"))
      (node (ref "K6") (pin "5") (pinfunction "NO1_5") (pintype "passive"))
      (node (ref "K7") (pin "1") (pinfunction "1_1") (pintype "passive"))
      (node (ref "K7") (pin "8") (pinfunction "NO2_8") (pintype "passive"))
    )
    (net (code "59") (name "Net-(K6C-NC2)") (class "Default")
      (node (ref "K6") (pin "7") (pinfunction "NC2_7") (pintype "passive"))
      (node (ref "K7") (pin "3") (pinfunction "COM1_3") (pintype "passive"))
    )
    (net (code "60") (name "Net-(K8B-NO1)") (class "Default")
      (node (ref "K8") (pin "5") (pinfunction "NO1_5") (pintype "passive"))
      (node (ref "K8") (pin "8") (pinfunction "NO2_8") (pintype "passive"))
    )
    (net (code "61") (name "unconnected-(J3-Pad6)") (class "Default")
      (node (ref "J3") (pin "6") (pintype "passive"))
    )
    (net (code "62") (name "unconnected-(J5-Pad5)") (class "Default")
      (node (ref "J5") (pin "5") (pintype "passive"))
    )
    (net (code "63") (name "unconnected-(J7-Pad2)") (class "Default")
      (node (ref "J7") (pin "2") (pintype "passive"))
    )
    (net (code "64") (name "unconnected-(K3B-NO1-Pad5)") (class "Default")
      (node (ref "K3") (pin "5") (pinfunction "NO1_5") (pintype "passive"))
    )
    (net (code "65") (name "unconnected-(K4B-NC1-Pad4)") (class "Default")
      (node (ref "K4") (pin "4") (pinfunction "NC1_4") (pintype "passive"))
    )
    (net (code "66") (name "unconnected-(K5B-NC1-Pad4)") (class "Default")
      (node (ref "K5") (pin "4") (pinfunction "NC1_4") (pintype "passive"))
    )
    (net (code "67") (name "unconnected-(K5C-NC2-Pad7)") (class "Default")
      (node (ref "K5") (pin "7") (pinfunction "NC2_7") (pintype "passive"))
    )
    (net (code "68") (name "unconnected-(K6C-NO2-Pad8)") (class "Default")
      (node (ref "K6") (pin "8") (pinfunction "NO2_8") (pintype "passive"))
    )
    (net (code "69") (name "unconnected-(K7B-NC1-Pad4)") (class "Default")
      (node (ref "K7") (pin "4") (pinfunction "NC1_4") (pintype "passive"))
    )
    (net (code "70") (name "unconnected-(K8B-NC1-Pad4)") (class "Default")
      (node (ref "K8") (pin "4") (pinfunction "NC1_4") (pintype "passive"))
    )
    (net (code "71") (name "unconnected-(K8C-NC2-Pad7)") (class "Default")
      (node (ref "K8") (pin "7") (pinfunction "NC2_7") (pintype "passive"))
    )
  )
)
